# LSM9DS1.net
KiCad netlist of a schematic drawn in EAGLE
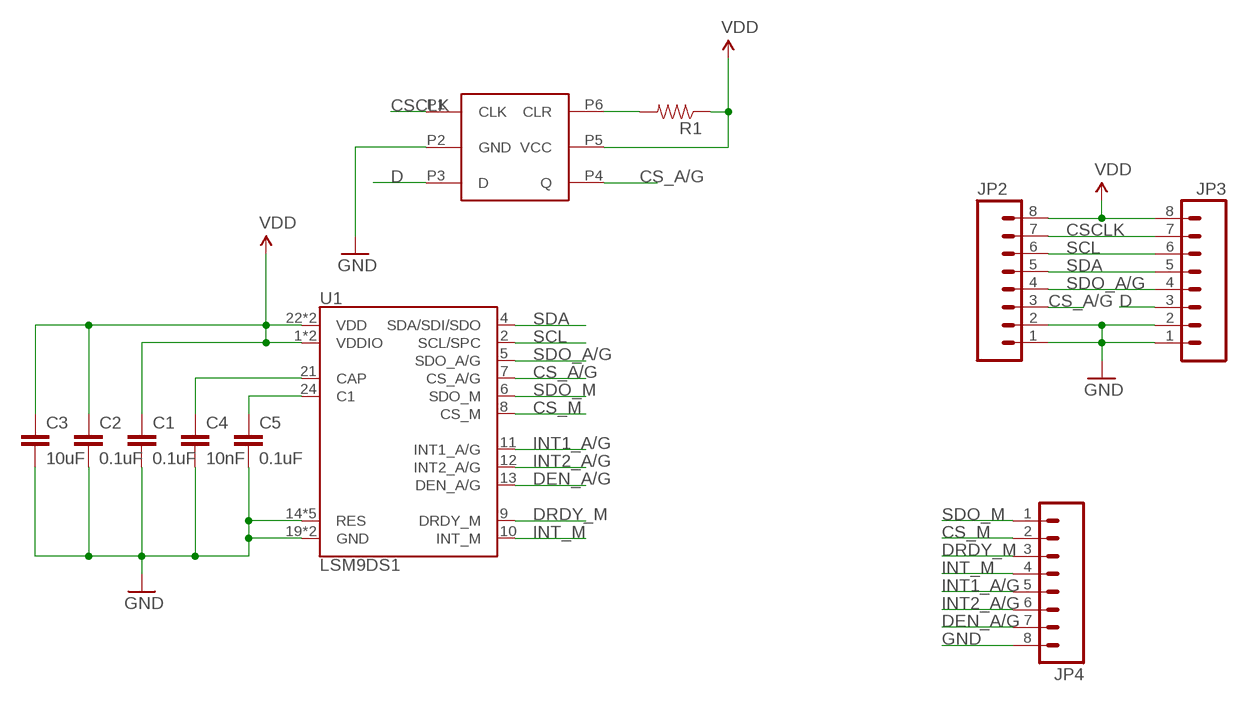
[diagram p0: schematic, sheet 1]

(export (version "E")
  (design (tool "Eeschema 10.0.6"))
  (components
    (comp (ref "C1")
      (value "0.1uF")
      (footprint "eagle-import:0603-CAP")
      (libsource (lib "eagle-import") (part "CAP0603-CAP"))
    )
    (comp (ref "C2")
      (value "0.1uF")
      (footprint "eagle-import:0603-CAP")
      (libsource (lib "eagle-import") (part "CAP0603-CAP"))
    )
    (comp (ref "C3")
      (value "10uF")
      (footprint "eagle-import:0603-CAP")
      (libsource (lib "eagle-import") (part "CAP0603-CAP"))
    )
    (comp (ref "C4")
      (value "10nF")
      (footprint "eagle-import:0603-CAP")
      (libsource (lib "eagle-import") (part "CAP0603-CAP"))
    )
    (comp (ref "C5")
      (value "0.1uF")
      (footprint "eagle-import:0603-CAP")
      (libsource (lib "eagle-import") (part "CAP0603-CAP"))
    )
    (comp (ref "JP2")
      (value "M08BM08B-SRSS-TB")
      (footprint "eagle-import:BM08B-SRSS-TB")
      (libsource (lib "eagle-import") (part "M08BM08B-SRSS-TB"))
    )
    (comp (ref "JP3")
      (value "M08BM08B-SRSS-TB")
      (footprint "eagle-import:BM08B-SRSS-TB")
      (libsource (lib "eagle-import") (part "M08BM08B-SRSS-TB"))
    )
    (comp (ref "JP4")
      (value "M08BM08B-SRSS-TB")
      (footprint "eagle-import:BM08B-SRSS-TB")
      (libsource (lib "eagle-import") (part "M08BM08B-SRSS-TB"))
    )
    (comp (ref "R1")
      (value "RESISTOR0603-RES")
      (footprint "eagle-import:0603-RES")
      (libsource (lib "eagle-import") (part "RESISTOR0603-RES"))
    )
    (comp (ref "U$1")
      (value "SN74LVC1G175")
      (footprint "eagle-import:SN74LVC1G175")
      (libsource (lib "eagle-import") (part "SN74LVC1G175"))
    )
    (comp (ref "U1")
      (value "LSM9DS1")
      (footprint "eagle-import:LGA24-8X4")
      (libsource (lib "eagle-import") (part "LSM9DS1"))
    )
  )
  (nets
    (net (code "1") (name "/CSCLK") (class "Default")
      (node (ref "JP2") (pin "7") (pinfunction "7_7") (pintype "passive"))
      (node (ref "JP3") (pin "7") (pinfunction "7_7") (pintype "passive"))
      (node (ref "U$1") (pin "P1") (pinfunction "CLK_P1") (pintype "bidirectional"))
    )
    (net (code "2") (name "/CS_A{slash}G") (class "Default")
      (node (ref "JP2") (pin "3") (pinfunction "3_3") (pintype "passive"))
      (node (ref "U$1") (pin "P4") (pinfunction "Q_P4") (pintype "bidirectional"))
      (node (ref "U1") (pin "7") (pinfunction "CS_A/G_7") (pintype "bidirectional"))
    )
    (net (code "3") (name "/CS_M") (class "Default")
      (node (ref "JP4") (pin "2") (pinfunction "2_2") (pintype "passive"))
      (node (ref "U1") (pin "8") (pinfunction "CS_M_8") (pintype "bidirectional"))
    )
    (net (code "4") (name "/D") (class "Default")
      (node (ref "JP3") (pin "3") (pinfunction "3_3") (pintype "passive"))
      (node (ref "U$1") (pin "P3") (pinfunction "D_P3") (pintype "bidirectional"))
    )
    (net (code "5") (name "/DEN_A{slash}G") (class "Default")
      (node (ref "JP4") (pin "7") (pinfunction "7_7") (pintype "passive"))
      (node (ref "U1") (pin "13") (pinfunction "DEN_A/G_13") (pintype "bidirectional"))
    )
    (net (code "6") (name "/DRDY_M") (class "Default")
      (node (ref "JP4") (pin "3") (pinfunction "3_3") (pintype "passive"))
      (node (ref "U1") (pin "9") (pinfunction "DRDY_M_9") (pintype "bidirectional"))
    )
    (net (code "7") (name "/INT1_A{slash}G") (class "Default")
      (node (ref "JP4") (pin "5") (pinfunction "5_5") (pintype "passive"))
      (node (ref "U1") (pin "11") (pinfunction "INT1_A/G_11") (pintype "bidirectional"))
    )
    (net (code "8") (name "/INT2_A{slash}G") (class "Default")
      (node (ref "JP4") (pin "6") (pinfunction "6_6") (pintype "passive"))
      (node (ref "U1") (pin "12") (pinfunction "INT2_A/G_12") (pintype "bidirectional"))
    )
    (net (code "9") (name "/INT_M") (class "Default")
      (node (ref "JP4") (pin "4") (pinfunction "4_4") (pintype "passive"))
      (node (ref "U1") (pin "10") (pinfunction "INT_M_10") (pintype "bidirectional"))
    )
    (net (code "10") (name "/SCL") (class "Default")
      (node (ref "JP2") (pin "6") (pinfunction "6_6") (pintype "passive"))
      (node (ref "JP3") (pin "6") (pinfunction "6_6") (pintype "passive"))
      (node (ref "U1") (pin "2") (pinfunction "SCL/SPC_2") (pintype "bidirectional"))
    )
    (net (code "11") (name "/SDA") (class "Default")
      (node (ref "JP2") (pin "5") (pinfunction "5_5") (pintype "passive"))
      (node (ref "JP3") (pin "5") (pinfunction "5_5") (pintype "passive"))
      (node (ref "U1") (pin "4") (pinfunction "SDA/SDI/SDO_4") (pintype "bidirectional"))
    )
    (net (code "12") (name "/SDO_A{slash}G") (class "Default")
      (node (ref "JP2") (pin "4") (pinfunction "4_4") (pintype "passive"))
      (node (ref "JP3") (pin "4") (pinfunction "4_4") (pintype "passive"))
      (node (ref "U1") (pin "5") (pinfunction "SDO_A/G_5") (pintype "bidirectional"))
    )
    (net (code "13") (name "/SDO_M") (class "Default")
      (node (ref "JP4") (pin "1") (pinfunction "1_1") (pintype "passive"))
      (node (ref "U1") (pin "6") (pinfunction "SDO_M_6") (pintype "bidirectional"))
    )
    (net (code "14") (name "GND") (class "Default")
      (node (ref "C1") (pin "2") (pinfunction "2_2") (pintype "passive"))
      (node (ref "C2") (pin "2") (pinfunction "2_2") (pintype "passive"))
      (node (ref "C3") (pin "2") (pinfunction "2_2") (pintype "passive"))
      (node (ref "C4") (pin "2") (pinfunction "2_2") (pintype "passive"))
      (node (ref "C5") (pin "2") (pinfunction "2_2") (pintype "passive"))
      (node (ref "JP2") (pin "1") (pinfunction "1_1") (pintype "passive"))
      (node (ref "JP2") (pin "2") (pinfunction "2_2") (pintype "passive"))
      (node (ref "JP3") (pin "1") (pinfunction "1_1") (pintype "passive"))
      (node (ref "JP3") (pin "2") (pinfunction "2_2") (pintype "passive"))
      (node (ref "JP4") (pin "8") (pinfunction "8_8") (pintype "passive"))
      (node (ref "U$1") (pin "P2") (pinfunction "GND_P2") (pintype "bidirectional"))
      (node (ref "U1") (pin "14") (pinfunction "RES_14") (pintype "bidirectional"))
      (node (ref "U1") (pin "15") (pinfunction "RES_15") (pintype "bidirectional"))
      (node (ref "U1") (pin "16") (pinfunction "RES_16") (pintype "bidirectional"))
      (node (ref "U1") (pin "17") (pinfunction "RES_17") (pintype "bidirectional"))
      (node (ref "U1") (pin "18") (pinfunction "RES_18") (pintype "bidirectional"))
      (node (ref "U1") (pin "19") (pinfunction "GND_19") (pintype "bidirectional"))
      (node (ref "U1") (pin "20") (pinfunction "GND_20") (pintype "bidirectional"))
    )
    (net (code "15") (name "Net-(U$1-CLR)") (class "Default")
      (node (ref "R1") (pin "2") (pinfunction "2_2") (pintype "passive"))
      (node (ref "U$1") (pin "P6") (pinfunction "CLR_P6") (pintype "bidirectional"))
    )
    (net (code "16") (name "Net-(U1-C1)") (class "Default")
      (node (ref "C5") (pin "1") (pinfunction "1_1") (pintype "passive"))
      (node (ref "U1") (pin "24") (pinfunction "C1_24") (pintype "bidirectional"))
    )
    (net (code "17") (name "Net-(U1-CAP)") (class "Default")
      (node (ref "C4") (pin "1") (pinfunction "1_1") (pintype "passive"))
      (node (ref "U1") (pin "21") (pinfunction "CAP_21") (pintype "bidirectional"))
    )
    (net (code "18") (name "VDD") (class "Default")
      (node (ref "C1") (pin "1") (pinfunction "1_1") (pintype "passive"))
      (node (ref "C2") (pin "1") (pinfunction "1_1") (pintype "passive"))
      (node (ref "C3") (pin "1") (pinfunction "1_1") (pintype "passive"))
      (node (ref "JP2") (pin "8") (pinfunction "8_8") (pintype "passive"))
      (node (ref "JP3") (pin "8") (pinfunction "8_8") (pintype "passive"))
      (node (ref "R1") (pin "1") (pinfunction "1_1") (pintype "passive"))
      (node (ref "U$1") (pin "P5") (pinfunction "VCC_P5") (pintype "bidirectional"))
      (node (ref "U1") (pin "1") (pinfunction "VDDIO_1") (pintype "bidirectional"))
      (node (ref "U1") (pin "22") (pinfunction "VDD_22") (pintype "bidirectional"))
      (node (ref "U1") (pin "23") (pinfunction "VDD_23") (pintype "bidirectional"))
      (node (ref "U1") (pin "3") (pinfunction "VDDIO_3") (pintype "bidirectional"))
    )
  )
)
